# Wacky_Racers_87557913.net
KiCad netlist of a schematic drawn in Altium Designer
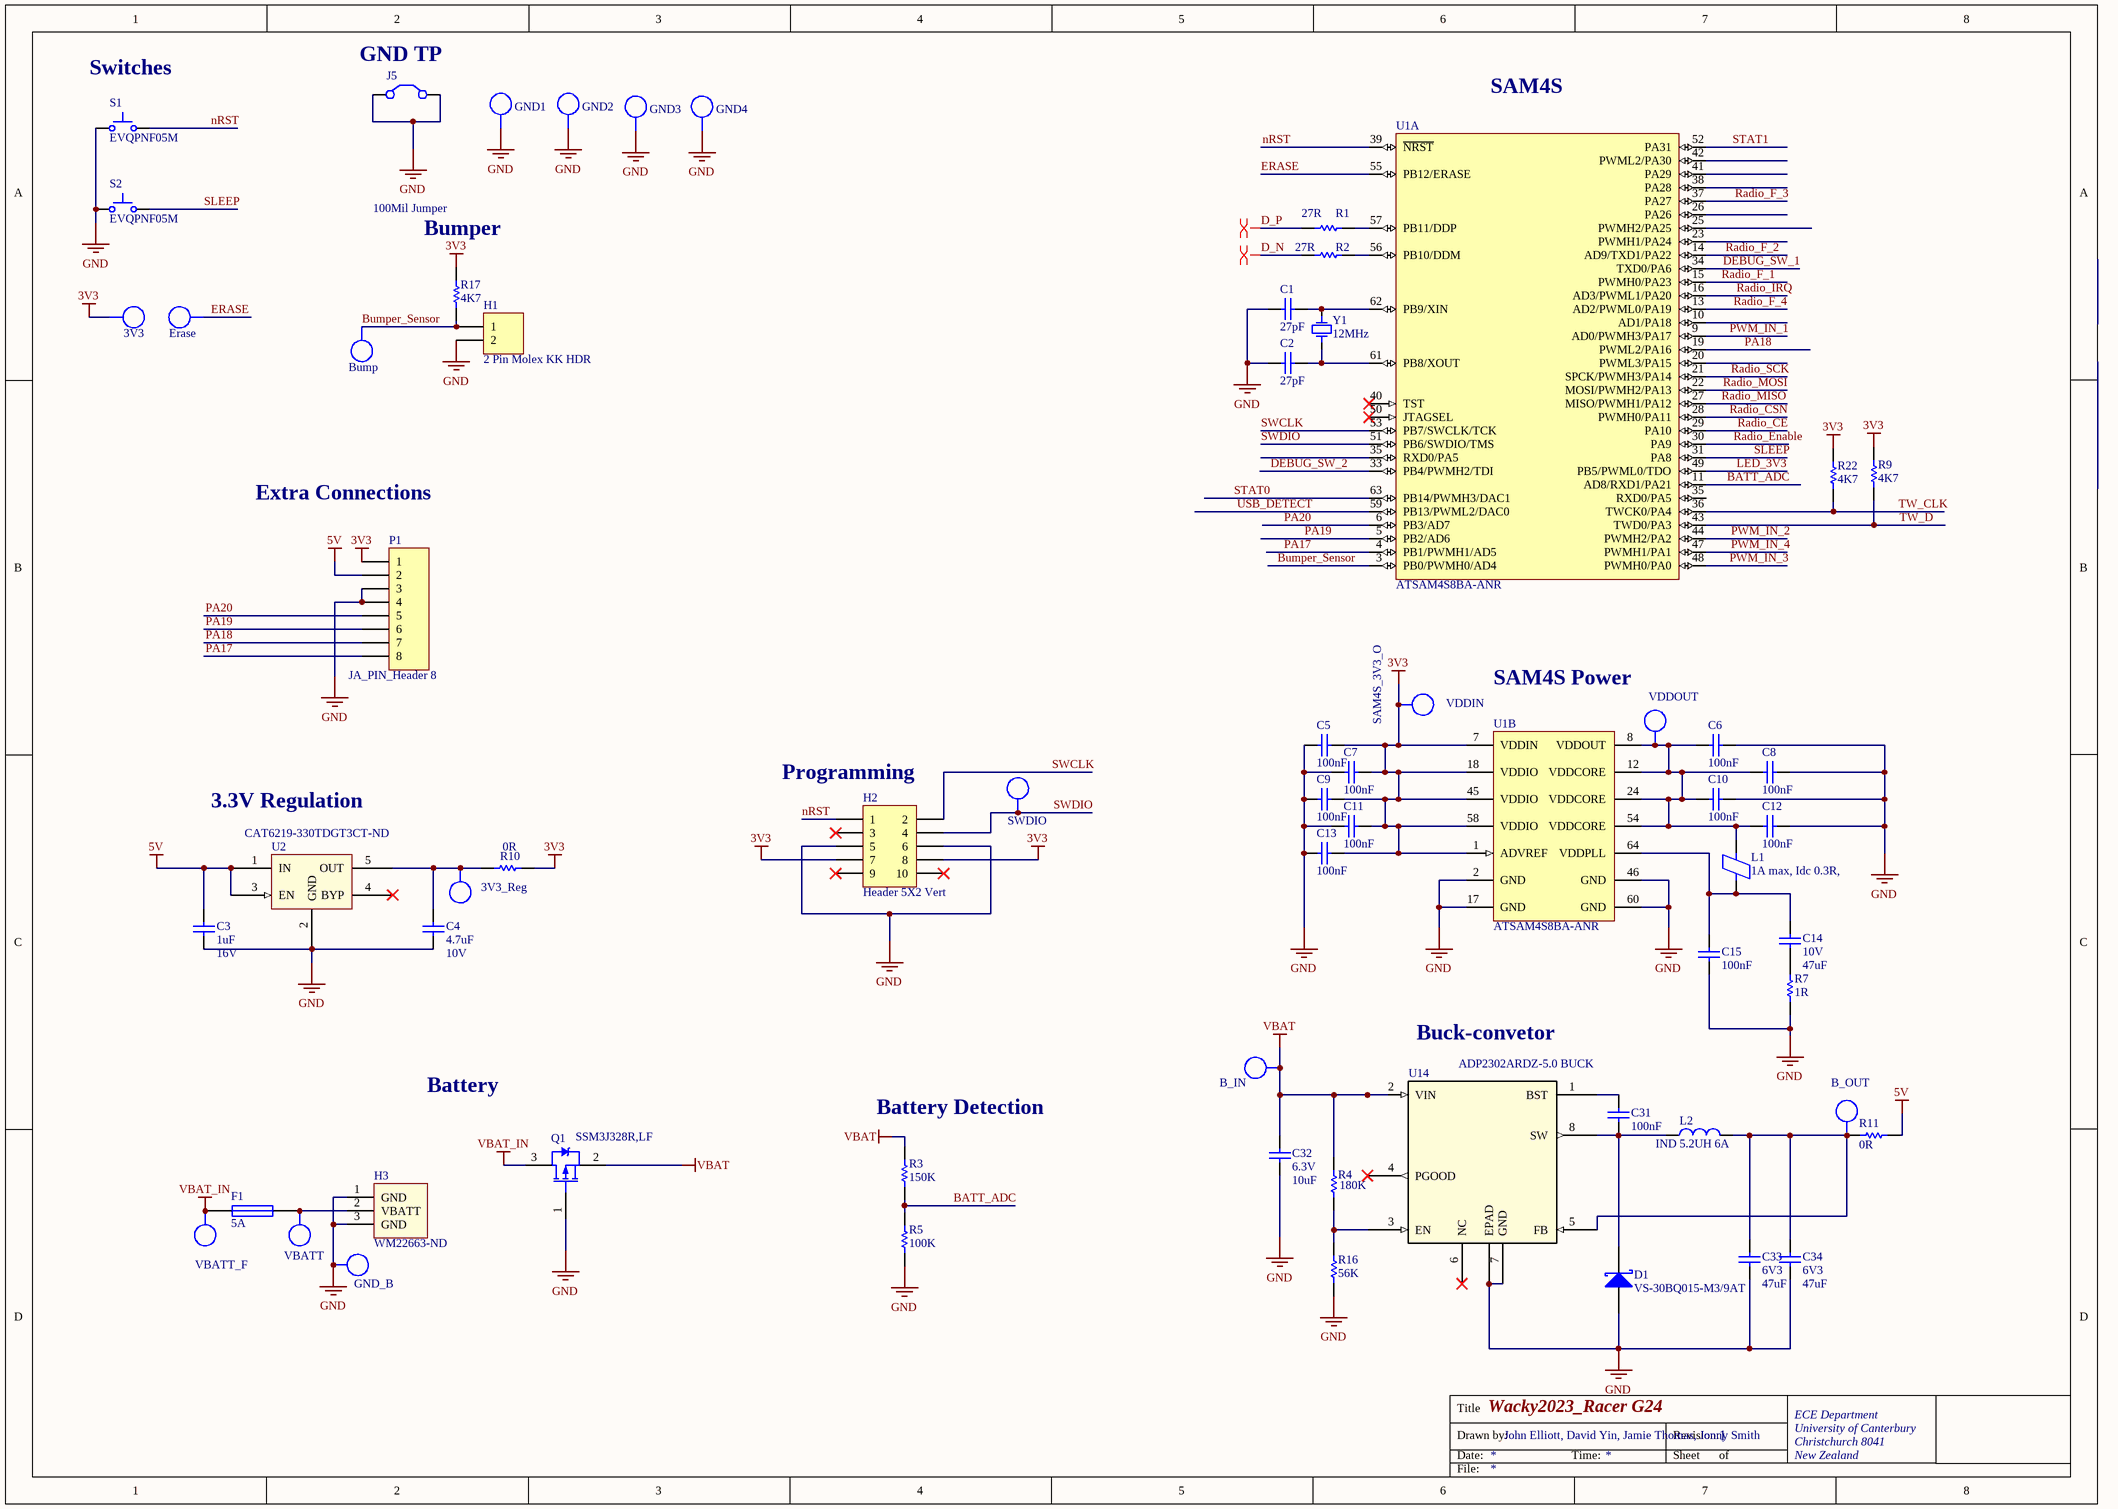
[diagram p0: Wacky_Racers_87557913.SchDoc]

(export (version "E")
  (design (tool "Eeschema 10.0.6"))
  (components
    (comp (ref "3V3")
      (value "TP")
      (footprint "TP_1206")
      (description "Test-Point 3.3x1.6x2.1mm SMD")
      (fields
        (field (name "MANUFACTURER") "Harwin Inc")
        (field (name "MANUFACTURER PART NUMBER") "S1751-46R")
      )
      (libsource (lib "ECE AD19Components_22V1") (part "TP_1206"))
    )
    (comp (ref "3V3_Reg")
      (value "TP")
      (footprint "TP_1206")
      (description "Test-Point 3.3x1.6x2.1mm SMD")
      (fields
        (field (name "MANUFACTURER") "Harwin Inc")
        (field (name "MANUFACTURER PART NUMBER") "S1751-46R")
      )
      (libsource (lib "ECE AD19Components_22V1") (part "TP_1206"))
    )
    (comp (ref "Bump")
      (value "TP")
      (footprint "TP_1206")
      (description "Test-Point 3.3x1.6x2.1mm SMD")
      (fields
        (field (name "MANUFACTURER") "Harwin Inc")
        (field (name "MANUFACTURER PART NUMBER") "S1751-46R")
      )
      (libsource (lib "ECE AD19Components_22V1") (part "TP_1206"))
    )
    (comp (ref "B_IN")
      (value "TP")
      (footprint "TP_1206")
      (description "Test-Point 3.3x1.6x2.1mm SMD")
      (fields
        (field (name "MANUFACTURER") "Harwin Inc")
        (field (name "MANUFACTURER PART NUMBER") "S1751-46R")
      )
      (libsource (lib "ECE AD19Components_22V1") (part "TP_1206"))
    )
    (comp (ref "B_OUT")
      (value "TP")
      (footprint "TP_1206")
      (description "Test-Point 3.3x1.6x2.1mm SMD")
      (fields
        (field (name "MANUFACTURER") "Harwin Inc")
        (field (name "MANUFACTURER PART NUMBER") "S1751-46R")
      )
      (libsource (lib "ECE AD19Components_22V1") (part "TP_1206"))
    )
    (comp (ref "C1")
      (value "27pF")
      (footprint "CAPC1608L")
      (description "CAP CER 27pF NPO/COG +-5% 50V 0603")
      (libsource (lib "ECE AD19Components_22V1") (part "CC_27pF_0603"))
    )
    (comp (ref "C2")
      (value "27pF")
      (footprint "CAPC1608L")
      (description "CAP CER 27pF NPO/COG +-5% 50V 0603")
      (libsource (lib "ECE AD19Components_22V1") (part "CC_27pF_0603"))
    )
    (comp (ref "C3")
      (value "1uF")
      (footprint "CAPC1608L")
      (description "CAP CER 1uF Y5V -20% +80% 16V 0603")
      (fields (field (name "MAX VOLTAGE") "16V"))
      (libsource (lib "ECE AD19Components_22V1") (part "CC_1uF_0603"))
    )
    (comp (ref "C4")
      (value "4.7uF")
      (footprint "CAPC1608N")
      (description "CAP CER 4.7uF X5R +-20%  10V 0603")
      (fields (field (name "MAX VOLTAGE") "10V"))
      (libsource (lib "ECE AD19Components_22V1") (part "CC_4.7uF_0603"))
    )
    (comp (ref "C5")
      (value "100nF")
      (footprint "CAPC1608L")
      (description "CAP CER 100nF X7R +-10% 50V 0603")
      (libsource (lib "ECE AD19Components_22V1") (part "CC_100nF_0603"))
    )
    (comp (ref "C6")
      (value "100nF")
      (footprint "CAPC1608L")
      (description "CAP CER 100nF X7R +-10% 50V 0603")
      (libsource (lib "ECE AD19Components_22V1") (part "CC_100nF_0603"))
    )
    (comp (ref "C7")
      (value "100nF")
      (footprint "CAPC1608L")
      (description "CAP CER 100nF X7R +-10% 50V 0603")
      (libsource (lib "ECE AD19Components_22V1") (part "CC_100nF_0603"))
    )
    (comp (ref "C8")
      (value "100nF")
      (footprint "CAPC1608L")
      (description "CAP CER 100nF X7R +-10% 50V 0603")
      (libsource (lib "ECE AD19Components_22V1") (part "CC_100nF_0603"))
    )
    (comp (ref "C9")
      (value "100nF")
      (footprint "CAPC1608L")
      (description "CAP CER 100nF X7R +-10% 50V 0603")
      (libsource (lib "ECE AD19Components_22V1") (part "CC_100nF_0603"))
    )
    (comp (ref "C10")
      (value "100nF")
      (footprint "CAPC1608L")
      (description "CAP CER 100nF X7R +-10% 50V 0603")
      (libsource (lib "ECE AD19Components_22V1") (part "CC_100nF_0603"))
    )
    (comp (ref "C11")
      (value "100nF")
      (footprint "CAPC1608L")
      (description "CAP CER 100nF X7R +-10% 50V 0603")
      (libsource (lib "ECE AD19Components_22V1") (part "CC_100nF_0603"))
    )
    (comp (ref "C12")
      (value "100nF")
      (footprint "CAPC1608L")
      (description "CAP CER 100nF X7R +-10% 50V 0603")
      (libsource (lib "ECE AD19Components_22V1") (part "CC_100nF_0603"))
    )
    (comp (ref "C13")
      (value "100nF")
      (footprint "CAPC1608L")
      (description "CAP CER 100nF X7R +-10% 50V 0603")
      (libsource (lib "ECE AD19Components_22V1") (part "CC_100nF_0603"))
    )
    (comp (ref "C14")
      (value "47uF")
      (footprint "CAPC3216L")
      (description "CAP CER 47uF X5R -/+20% 10V 1206")
      (fields (field (name "MAX VOLTAGE") "10V"))
      (libsource (lib "ECE AD19Components_22V1") (part "CC_47uF_1206"))
    )
    (comp (ref "C15")
      (value "100nF")
      (footprint "CAPC1608L")
      (description "CAP CER 100nF X7R +-10% 50V 0603")
      (libsource (lib "ECE AD19Components_22V1") (part "CC_100nF_0603"))
    )
    (comp (ref "C31")
      (value "100nF")
      (footprint "CAPC1608L")
      (description "CAP CER 100nF X7R +-10% 50V 0603")
      (libsource (lib "ECE AD19Components_22V1") (part "CC_100nF_0603"))
    )
    (comp (ref "C32")
      (value "10uF")
      (footprint "CAPC1608L")
      (description "CAP CER 10UF X5R +-20% 6V3 0603")
      (fields (field (name "VOLTAGE - RATED") "6.3V"))
      (libsource (lib "ECE AD19Components_22V1") (part "CC_10uF_0603"))
    )
    (comp (ref "C33")
      (value "CC_47uF_0805_6V3")
      (footprint "CAPC2012N")
      (description "SAMSUNG ELECTRO-MECHANICS - CL21A476MQCLRNC - CAP, 47UF, 6.3V, MLCC, 0805")
      (fields
        (field (name "TOLERANCE") "20%")
        (field (name "VOLTAGE RATING") "6V3")
        (field (name "CAPACITANCE") "47uF")
      )
      (libsource (lib "ECE AD19Components_22V1") (part "CC_47uF_0805_6V3"))
    )
    (comp (ref "C34")
      (value "CC_47uF_0805_6V3")
      (footprint "CAPC2012N")
      (description "SAMSUNG ELECTRO-MECHANICS - CL21A476MQCLRNC - CAP, 47UF, 6.3V, MLCC, 0805")
      (fields
        (field (name "TOLERANCE") "20%")
        (field (name "VOLTAGE RATING") "6V3")
        (field (name "CAPACITANCE") "47uF")
      )
      (libsource (lib "ECE AD19Components_22V1") (part "CC_47uF_0805_6V3"))
    )
    (comp (ref "D1")
      (value "VS-30BQ015-M3/9AT")
      (footprint "SMC")
      (description "DIODE, SCHOTTKY, 3A, 15V, DO-214AB / SMC")
      (fields (field (name "MANUFACTURER") "Vishay Semiconductors"))
      (libsource (lib "ECE AD19Components_22V1") (part "DS_VS-30BQ015-M3"))
    )
    (comp (ref "Erase")
      (value "TP")
      (footprint "TP_1206")
      (description "Test-Point 3.3x1.6x2.1mm SMD")
      (fields
        (field (name "MANUFACTURER") "Harwin Inc")
        (field (name "MANUFACTURER PART NUMBER") "S1751-46R")
      )
      (libsource (lib "ECE AD19Components_22V1") (part "TP_1206"))
    )
    (comp (ref "F1")
      (value "5A")
      (footprint "RESC3216N")
      (description "Fuse 5.0A Fast Acting 1206 SMD")
      (fields (field (name "MANUFACTURER PART NUMBER") "C1F5") (field (name "MANUFACTURER") "Bel TRP"))
      (libsource (lib "ECE AD19Components_22V1") (part "FS_Fuse_5.0A"))
    )
    (comp (ref "GND1")
      (value "TP")
      (footprint "TP_1206")
      (description "Test-Point 3.3x1.6x2.1mm SMD")
      (fields
        (field (name "MANUFACTURER") "Harwin Inc")
        (field (name "MANUFACTURER PART NUMBER") "S1751-46R")
      )
      (libsource (lib "ECE AD19Components_22V1") (part "TP_1206"))
    )
    (comp (ref "GND2")
      (value "TP")
      (footprint "TP_1206")
      (description "Test-Point 3.3x1.6x2.1mm SMD")
      (fields
        (field (name "MANUFACTURER") "Harwin Inc")
        (field (name "MANUFACTURER PART NUMBER") "S1751-46R")
      )
      (libsource (lib "ECE AD19Components_22V1") (part "TP_1206"))
    )
    (comp (ref "GND3")
      (value "TP")
      (footprint "TP_1206")
      (description "Test-Point 3.3x1.6x2.1mm SMD")
      (fields
        (field (name "MANUFACTURER") "Harwin Inc")
        (field (name "MANUFACTURER PART NUMBER") "S1751-46R")
      )
      (libsource (lib "ECE AD19Components_22V1") (part "TP_1206"))
    )
    (comp (ref "GND4")
      (value "TP")
      (footprint "TP_1206")
      (description "Test-Point 3.3x1.6x2.1mm SMD")
      (fields
        (field (name "MANUFACTURER") "Harwin Inc")
        (field (name "MANUFACTURER PART NUMBER") "S1751-46R")
      )
      (libsource (lib "ECE AD19Components_22V1") (part "TP_1206"))
    )
    (comp (ref "GND_B")
      (value "TP")
      (footprint "TP_1206")
      (description "Test-Point 3.3x1.6x2.1mm SMD")
      (fields
        (field (name "MANUFACTURER") "Harwin Inc")
        (field (name "MANUFACTURER PART NUMBER") "S1751-46R")
      )
      (libsource (lib "ECE AD19Components_22V1") (part "TP_1206"))
    )
    (comp (ref "H1")
      (value "2 Pin Molex KK HDR")
      (footprint "MOLEX_KK_2_HDR")
      (description "CONN HEADER 2POS 2.54mm VERT_Thru Hole")
      (libsource (lib "ECE AD19Components_22V1") (part "JA_MOLEX_KK_2POS"))
    )
    (comp (ref "H2")
      (value "Header 5X2 Vert")
      (footprint "IDC2.54-V10D")
      (description "IDC Header, 2,54mm, 10-Pin, Vert")
      (libsource (lib "ECE AD19Components_22V1") (part "JA_HDR_IDC_5X2_VERT"))
    )
    (comp (ref "H3")
      (value "Battery_HEADER_3pin")
      (footprint "BATT_HEADER_3POS")
      (description "3Pin Header 2.54mm spacing\r\nDigikey #WM22663-ND")
      (fields (field (name "SUPPLIER PART NUMBER 1") "WM22663-ND"))
      (libsource (lib "ENCE461AD19_V23") (part "Battery_HEADER_3pin"))
    )
    (comp (ref "J5")
      (value "100Mil Jumper")
      (footprint "JMP2.54")
      (description "2.54mm Jumper Thru Hole")
      (libsource (lib "ECE AD19Components_22V1") (part "TP_JUMPER"))
    )
    (comp (ref "L1")
      (value "1A max, Idc 0.3R,")
      (footprint "INDC3216L")
      (description "Ferrite Bead, Rdc 0.3R, Z100MHZ 600R, Imax 1A, SMD 1206")
      (fields
        (field (name "MANUFACTURER") "FAIR-RITE")
        (field (name "MANUFACTURER PART NUMBER") "2512066017Y1")
      )
      (libsource (lib "ECE AD19Components_22V1") (part "IN_Ferrite-Bead"))
    )
    (comp (ref "L2")
      (value "IND 5.2UH 6A")
      (footprint "INDUCTOR5u2")
      (description "FIXED IND 5.2UH 6A 22 MOHM SMD")
      (fields
        (field (name "MANUFACTURER") "Sumida America Components Inc.")
        (field (name "MANUFACTURER PART NUMBER") "CDRH104RNP-5R2NC")
      )
      (libsource (lib "ENCE461AD19_V23") (part "CDRH104RNP-5R2NC"))
    )
    (comp (ref "P1")
      (value "JA_PIN_Header 8")
      (footprint "HDR1X8")
      (description "Header, 8-Pin")
      (fields (field (name "PUBLISHER") "Altium Limited"))
      (libsource (lib "ECE AD19Components_22V1") (part "JA_PIN_Header 8"))
    )
    (comp (ref "Q1")
      (value "SSM3J328R,LF")
      (footprint "SOT23_L")
      (description "MOSFET P-CH 20V 6A SOT23-3")
      (fields
        (field (name "MANUFACTURER") "Toshiba")
        (field (name "MANUFACTURER PART NUMBER") "SSM3J328R,LF")
      )
      (libsource (lib "ECE AD19Components_22V1") (part "TM_SSM3J328R"))
    )
    (comp (ref "R1")
      (value "27R")
      (footprint "RESC1608L")
      (description "RES 27 OHM 1/10W 5% 0603 SMD")
      (libsource (lib "ECE AD19Components_22V1") (part "RS_27R"))
    )
    (comp (ref "R2")
      (value "27R")
      (footprint "RESC1608L")
      (description "RES 27 OHM 1/10W 5% 0603 SMD")
      (libsource (lib "ECE AD19Components_22V1") (part "RS_27R"))
    )
    (comp (ref "R3")
      (value "150K")
      (footprint "RESC1608L")
      (description "RES 150K OHM 1/10W 5% 0603 SMD")
      (libsource (lib "ECE AD19Components_22V1") (part "RS_150K"))
    )
    (comp (ref "R4")
      (value "180K")
      (footprint "RESC1608L")
      (description "RES 180K OHM 1/10W 5% 0603 SMD")
      (libsource (lib "ECE AD19Components_22V1") (part "RS_180K"))
    )
    (comp (ref "R5")
      (value "100K")
      (footprint "RESC1608L")
      (description "RES 100K OHM 1/10W 5% 0603 SMD")
      (libsource (lib "ECE AD19Components_22V1") (part "RS_100K"))
    )
    (comp (ref "R7")
      (value "1R")
      (footprint "RESC3216L")
      (description "RES 1R OHM 1/4W 5% 1206 SMD")
      (libsource (lib "ECE AD19Components_22V1") (part "RT_1R"))
    )
    (comp (ref "R9")
      (value "4K7")
      (footprint "RESC1608L")
      (description "RES 4.7K OHM 1/10W 5% 0603 SMD")
      (libsource (lib "ECE AD19Components_22V1") (part "RS_4K7"))
    )
    (comp (ref "R10")
      (value "0R")
      (footprint "RESC1608L")
      (description "RES 0.0 OHM 1/10W 5% 0603 SMD")
      (libsource (lib "ECE AD19Components_22V1") (part "RS_0R0"))
    )
    (comp (ref "R11")
      (value "0R")
      (footprint "RESC1608L")
      (description "RES 0.0 OHM 1/10W 5% 0603 SMD")
      (libsource (lib "ECE AD19Components_22V1") (part "RS_0R0"))
    )
    (comp (ref "R16")
      (value "56K")
      (footprint "RESC1608L")
      (description "RES 56.0K OHM 1/10W 5% 0603 SMD")
      (libsource (lib "ECE AD19Components_22V1") (part "RS_56K"))
    )
    (comp (ref "R17")
      (value "4K7")
      (footprint "RESC1608L")
      (description "RES 4.7K OHM 1/10W 5% 0603 SMD")
      (libsource (lib "ECE AD19Components_22V1") (part "RS_4K7"))
    )
    (comp (ref "R22")
      (value "4K7")
      (footprint "RESC1608L")
      (description "RES 4.7K OHM 1/10W 5% 0603 SMD")
      (libsource (lib "ECE AD19Components_22V1") (part "RS_4K7"))
    )
    (comp (ref "S1")
      (value "EVQPNF05M")
      (footprint "EVQPNF05M")
      (description "Panasonic 6 x 3.5mm SMD Light Touch Switch Type SMD")
      (fields (field (name "MANUFACTURER") "Panasonic"))
      (libsource (lib "ECE AD19Components_22V1") (part "WS_EVQPNF05M"))
    )
    (comp (ref "S2")
      (value "EVQPNF05M")
      (footprint "EVQPNF05M")
      (description "Panasonic 6 x 3.5mm SMD Light Touch Switch Type SMD")
      (fields (field (name "MANUFACTURER") "Panasonic"))
      (libsource (lib "ECE AD19Components_22V1") (part "WS_EVQPNF05M"))
    )
    (comp (ref "SWDIO")
      (value "TP")
      (footprint "TP_1206")
      (description "Test-Point 3.3x1.6x2.1mm SMD")
      (fields
        (field (name "MANUFACTURER") "Harwin Inc")
        (field (name "MANUFACTURER PART NUMBER") "S1751-46R")
      )
      (libsource (lib "ECE AD19Components_22V1") (part "TP_1206"))
    )
    (comp (ref "U1")
      (value "ATSAM4S8BA-ANR")
      (footprint "LQFP64_L")
      (description "IC MCU 32BIT 512KB FLASH 64LQFP")
      (fields (field (name "MANUFACTURER") "Atmel"))
      (libsource (lib "ECE AD19Components_22V1") (part "SE_ATSAM4S16BA-MU"))
    )
    (comp (ref "U2")
      (value "CAT6219-330TDGT3")
      (footprint "SOT95P280X145-5N")
      (description "IC REG LIN 3.3V 500MA TSOT23-5")
      (fields
        (field (name "BASE PART NUMBER") "CAT6219")
        (field (name "SUPPLIER PART NUMBER") "CAT6219-330TDGT3CT-ND")
      )
      (libsource (lib "ENCE461AD19_V23") (part "SV_CAT6219-330TDGT3"))
    )
    (comp (ref "U14")
      (value "ADP2302ARDZ-5.0 BUCK")
      (footprint "RD_8_1")
      (description "IC REG BUCK 5V 2A 8SOIC")
      (fields (field (name "MANUFACTURER_PART_NUMBER") "ADP2302ARDZ-5.0-R7"))
      (libsource (lib "ENCE461AD19_V23") (part "ADP2302ARDZ-5.0-R7"))
    )
    (comp (ref "VBATT")
      (value "TP")
      (footprint "TP_1206")
      (description "Test-Point 3.3x1.6x2.1mm SMD")
      (fields
        (field (name "MANUFACTURER") "Harwin Inc")
        (field (name "MANUFACTURER PART NUMBER") "S1751-46R")
      )
      (libsource (lib "ECE AD19Components_22V1") (part "TP_1206"))
    )
    (comp (ref "VBATT_F")
      (value "TP")
      (footprint "TP_1206")
      (description "Test-Point 3.3x1.6x2.1mm SMD")
      (fields
        (field (name "MANUFACTURER") "Harwin Inc")
        (field (name "MANUFACTURER PART NUMBER") "S1751-46R")
      )
      (libsource (lib "ECE AD19Components_22V1") (part "TP_1206"))
    )
    (comp (ref "VDDIN")
      (value "TP")
      (footprint "TP_1206")
      (description "Test-Point 3.3x1.6x2.1mm SMD")
      (fields
        (field (name "MANUFACTURER") "Harwin Inc")
        (field (name "MANUFACTURER PART NUMBER") "S1751-46R")
      )
      (libsource (lib "ECE AD19Components_22V1") (part "TP_1206"))
    )
    (comp (ref "VDDOUT")
      (value "TP")
      (footprint "TP_1206")
      (description "Test-Point 3.3x1.6x2.1mm SMD")
      (fields
        (field (name "MANUFACTURER") "Harwin Inc")
        (field (name "MANUFACTURER PART NUMBER") "S1751-46R")
      )
      (libsource (lib "ECE AD19Components_22V1") (part "TP_1206"))
    )
    (comp (ref "Y1")
      (value "12MHz")
      (footprint "6.0X3.5-4")
      (description "CRYSTAL 12MHZ 18PF 6X3.5mm SMD")
      (fields
        (field (name "MANUFACTURER") "CTS-Frequency Controls")
        (field (name "MANUFACTURER PART NUMBER") "406C35D12M00000")
        (field (name "FREQUENCY") "12MHz")
      )
      (libsource (lib "ECE AD19Components_22V1") (part "XT_CRYSTAL_12MHz_18pF"))
    )
  )
  (nets
    (net (code "1") (name "/BATT_ADC") (class "Default")
      (node (ref "R3") (pin "1") (pinfunction "1_1") (pintype "passive"))
      (node (ref "R5") (pin "2") (pinfunction "2_2") (pintype "passive"))
      (node (ref "U1") (pin "11") (pinfunction "AD8/RXD1/PA21_11") (pintype "bidirectional"))
    )
    (net (code "2") (name "/Bumper_Sensor") (class "Default")
      (node (ref "Bump") (pin "1") (pinfunction "1_1") (pintype "passive"))
      (node (ref "H1") (pin "1") (pinfunction "1_1") (pintype "passive"))
      (node (ref "R17") (pin "1") (pinfunction "1_1") (pintype "passive"))
      (node (ref "U1") (pin "3") (pinfunction "PB0/PWMH0/AD4_3") (pintype "bidirectional"))
    )
    (net (code "3") (name "/DEBUG_SW_1") (class "Default")
      (node (ref "U1") (pin "34") (pinfunction "TXD0/PA6_34") (pintype "bidirectional"))
    )
    (net (code "4") (name "/DEBUG_SW_2") (class "Default")
      (node (ref "U1") (pin "33") (pinfunction "PB4/PWMH2/TDI_33") (pintype "bidirectional"))
    )
    (net (code "5") (name "/D_N") (class "Default")
      (node (ref "R2") (pin "1") (pinfunction "1_1") (pintype "passive"))
    )
    (net (code "6") (name "/D_P") (class "Default")
      (node (ref "R1") (pin "1") (pinfunction "1_1") (pintype "passive"))
    )
    (net (code "7") (name "/ERASE") (class "Default")
      (node (ref "Erase") (pin "1") (pinfunction "1_1") (pintype "passive"))
      (node (ref "U1") (pin "55") (pinfunction "PB12/ERASE_55") (pintype "bidirectional"))
    )
    (net (code "8") (name "/LED_3V3") (class "Default")
      (node (ref "U1") (pin "49") (pinfunction "PB5/PWML0/TDO_49") (pintype "bidirectional"))
    )
    (net (code "9") (name "/PA17") (class "Default")
      (node (ref "P1") (pin "8") (pinfunction "8_8") (pintype "passive"))
      (node (ref "U1") (pin "4") (pinfunction "PB1/PWMH1/AD5_4") (pintype "bidirectional"))
    )
    (net (code "10") (name "/PA18") (class "Default")
      (node (ref "P1") (pin "7") (pinfunction "7_7") (pintype "passive"))
      (node (ref "U1") (pin "19") (pinfunction "PWML2/PA16_19") (pintype "bidirectional"))
    )
    (net (code "11") (name "/PA19") (class "Default")
      (node (ref "P1") (pin "6") (pinfunction "6_6") (pintype "passive"))
      (node (ref "U1") (pin "5") (pinfunction "PB2/AD6_5") (pintype "bidirectional"))
    )
    (net (code "12") (name "/PA20") (class "Default")
      (node (ref "P1") (pin "5") (pinfunction "5_5") (pintype "passive"))
      (node (ref "U1") (pin "6") (pinfunction "PB3/AD7_6") (pintype "bidirectional"))
    )
    (net (code "13") (name "/PWM_IN_1") (class "Default")
      (node (ref "U1") (pin "9") (pinfunction "AD0/PWMH3/PA17_9") (pintype "bidirectional"))
    )
    (net (code "14") (name "/PWM_IN_2") (class "Default")
      (node (ref "U1") (pin "44") (pinfunction "PWMH2/PA2_44") (pintype "bidirectional"))
    )
    (net (code "15") (name "/PWM_IN_3") (class "Default")
      (node (ref "U1") (pin "48") (pinfunction "PWMH0/PA0_48") (pintype "bidirectional"))
    )
    (net (code "16") (name "/PWM_IN_4") (class "Default")
      (node (ref "U1") (pin "47") (pinfunction "PWMH1/PA1_47") (pintype "bidirectional"))
    )
    (net (code "17") (name "/Radio_CE") (class "Default")
      (node (ref "U1") (pin "29") (pinfunction "PA10_29") (pintype "bidirectional"))
    )
    (net (code "18") (name "/Radio_CSN") (class "Default")
      (node (ref "U1") (pin "28") (pinfunction "PWMH0/PA11_28") (pintype "bidirectional"))
    )
    (net (code "19") (name "/Radio_Enable") (class "Default")
      (node (ref "U1") (pin "30") (pinfunction "PA9_30") (pintype "bidirectional"))
    )
    (net (code "20") (name "/Radio_F_1") (class "Default")
      (node (ref "U1") (pin "15") (pinfunction "PWMH0/PA23_15") (pintype "bidirectional"))
    )
    (net (code "21") (name "/Radio_F_2") (class "Default")
      (node (ref "U1") (pin "14") (pinfunction "AD9/TXD1/PA22_14") (pintype "bidirectional"))
    )
    (net (code "22") (name "/Radio_F_3") (class "Default")
      (node (ref "U1") (pin "37") (pinfunction "PA27_37") (pintype "bidirectional"))
    )
    (net (code "23") (name "/Radio_F_4") (class "Default")
      (node (ref "U1") (pin "13") (pinfunction "AD2/PWML0/PA19_13") (pintype "bidirectional"))
    )
    (net (code "24") (name "/Radio_IRQ") (class "Default")
      (node (ref "U1") (pin "16") (pinfunction "AD3/PWML1/PA20_16") (pintype "bidirectional"))
    )
    (net (code "25") (name "/Radio_MISO") (class "Default")
      (node (ref "U1") (pin "27") (pinfunction "MISO/PWMH1/PA12_27") (pintype "bidirectional"))
    )
    (net (code "26") (name "/Radio_MOSI") (class "Default")
      (node (ref "U1") (pin "22") (pinfunction "MOSI/PWMH2/PA13_22") (pintype "bidirectional"))
    )
    (net (code "27") (name "/Radio_SCK") (class "Default")
      (node (ref "U1") (pin "21") (pinfunction "SPCK/PWMH3/PA14_21") (pintype "bidirectional"))
    )
    (net (code "28") (name "/SLEEP") (class "Default")
      (node (ref "S2") (pin "2") (pintype "passive"))
      (node (ref "U1") (pin "31") (pinfunction "PA8_31") (pintype "bidirectional"))
    )
    (net (code "29") (name "/STAT0") (class "Default")
      (node (ref "U1") (pin "63") (pinfunction "PB14/PWMH3/DAC1_63") (pintype "bidirectional"))
    )
    (net (code "30") (name "/STAT1") (class "Default")
      (node (ref "U1") (pin "52") (pinfunction "PA31_52") (pintype "bidirectional"))
    )
    (net (code "31") (name "/SWCLK") (class "Default")
      (node (ref "H2") (pin "2") (pinfunction "2_2") (pintype "passive"))
      (node (ref "U1") (pin "53") (pinfunction "PB7/SWCLK/TCK_53") (pintype "bidirectional"))
    )
    (net (code "32") (name "/SWDIO") (class "Default")
      (node (ref "H2") (pin "4") (pinfunction "4_4") (pintype "passive"))
      (node (ref "SWDIO") (pin "1") (pinfunction "1_1") (pintype "passive"))
      (node (ref "U1") (pin "51") (pinfunction "PB6/SWDIO/TMS_51") (pintype "bidirectional"))
    )
    (net (code "33") (name "/TW_CLK") (class "Default")
      (node (ref "R22") (pin "2") (pinfunction "2_2") (pintype "passive"))
      (node (ref "U1") (pin "36") (pinfunction "TWCK0/PA4_36") (pintype "bidirectional"))
    )
    (net (code "34") (name "/TW_D") (class "Default")
      (node (ref "R9") (pin "2") (pinfunction "2_2") (pintype "passive"))
      (node (ref "U1") (pin "43") (pinfunction "TWD0/PA3_43") (pintype "bidirectional"))
    )
    (net (code "35") (name "/USB_DETECT") (class "Default")
      (node (ref "U1") (pin "59") (pinfunction "PB13/PWML2/DAC0_59") (pintype "bidirectional"))
    )
    (net (code "36") (name "/nRST") (class "Default")
      (node (ref "H2") (pin "1") (pinfunction "1_1") (pintype "passive"))
      (node (ref "S1") (pin "2") (pintype "passive"))
      (node (ref "U1") (pin "39") (pinfunction "~{NRST}_39") (pintype "bidirectional"))
    )
    (net (code "37") (name "3V3") (class "Default")
      (node (ref "3V3") (pin "1") (pinfunction "1_1") (pintype "passive"))
      (node (ref "C11") (pin "2") (pinfunction "2_2") (pintype "passive"))
      (node (ref "C13") (pin "1") (pinfunction "1_1") (pintype "passive"))
      (node (ref "C5") (pin "2") (pinfunction "2_2") (pintype "passive"))
      (node (ref "C7") (pin "2") (pinfunction "2_2") (pintype "passive"))
      (node (ref "C9") (pin "2") (pinfunction "2_2") (pintype "passive"))
      (node (ref "H2") (pin "7") (pinfunction "7_7") (pintype "passive"))
      (node (ref "H2") (pin "8") (pinfunction "8_8") (pintype "passive"))
      (node (ref "P1") (pin "1") (pinfunction "1_1") (pintype "passive"))
      (node (ref "R10") (pin "2") (pinfunction "2_2") (pintype "passive"))
      (node (ref "R17") (pin "2") (pinfunction "2_2") (pintype "passive"))
      (node (ref "R22") (pin "1") (pinfunction "1_1") (pintype "passive"))
      (node (ref "R9") (pin "1") (pinfunction "1_1") (pintype "passive"))
      (node (ref "U1") (pin "1") (pinfunction "ADVREF_1") (pintype "input"))
      (node (ref "U1") (pin "18") (pinfunction "VDDIO_18") (pintype "power_in"))
      (node (ref "U1") (pin "45") (pinfunction "VDDIO_45") (pintype "power_in"))
      (node (ref "U1") (pin "58") (pinfunction "VDDIO_58") (pintype "power_in"))
      (node (ref "U1") (pin "7") (pinfunction "VDDIN_7") (pintype "power_in"))
      (node (ref "VDDIN") (pin "1") (pinfunction "1_1") (pintype "passive"))
    )
    (net (code "38") (name "5V") (class "Default")
      (node (ref "C3") (pin "2") (pinfunction "2_2") (pintype "passive"))
      (node (ref "P1") (pin "2") (pinfunction "2_2") (pintype "passive"))
      (node (ref "R11") (pin "1") (pinfunction "1_1") (pintype "passive"))
      (node (ref "U2") (pin "1") (pinfunction "IN_1") (pintype "power_in"))
      (node (ref "U2") (pin "3") (pinfunction "EN_3") (pintype "input"))
    )
    (net (code "39") (name "GND") (class "Default")
      (node (ref "C1") (pin "1") (pinfunction "1_1") (pintype "passive"))
      (node (ref "C10") (pin "2") (pinfunction "2_2") (pintype "passive"))
      (node (ref "C11") (pin "1") (pinfunction "1_1") (pintype "passive"))
      (node (ref "C12") (pin "2") (pinfunction "2_2") (pintype "passive"))
      (node (ref "C13") (pin "2") (pinfunction "2_2") (pintype "passive"))
      (node (ref "C15") (pin "1") (pinfunction "1_1") (pintype "passive"))
      (node (ref "C2") (pin "1") (pinfunction "1_1") (pintype "passive"))
      (node (ref "C3") (pin "1") (pinfunction "1_1") (pintype "passive"))
      (node (ref "C32") (pin "1") (pinfunction "1_1") (pintype "passive"))
      (node (ref "C33") (pin "1") (pinfunction "1_1") (pintype "passive"))
      (node (ref "C34") (pin "1") (pinfunction "1_1") (pintype "passive"))
      (node (ref "C4") (pin "1") (pinfunction "1_1") (pintype "passive"))
      (node (ref "C5") (pin "1") (pinfunction "1_1") (pintype "passive"))
      (node (ref "C6") (pin "2") (pinfunction "2_2") (pintype "passive"))
      (node (ref "C7") (pin "1") (pinfunction "1_1") (pintype "passive"))
      (node (ref "C8") (pin "2") (pinfunction "2_2") (pintype "passive"))
      (node (ref "C9") (pin "1") (pinfunction "1_1") (pintype "passive"))
      (node (ref "D1") (pin "1") (pinfunction "A_1") (pintype "passive"))
      (node (ref "GND1") (pin "1") (pinfunction "1_1") (pintype "passive"))
      (node (ref "GND2") (pin "1") (pinfunction "1_1") (pintype "passive"))
      (node (ref "GND3") (pin "1") (pinfunction "1_1") (pintype "passive"))
      (node (ref "GND4") (pin "1") (pinfunction "1_1") (pintype "passive"))
      (node (ref "GND_B") (pin "1") (pinfunction "1_1") (pintype "passive"))
      (node (ref "H1") (pin "2") (pinfunction "2_2") (pintype "passive"))
      (node (ref "H2") (pin "5") (pinfunction "5_5") (pintype "passive"))
      (node (ref "H2") (pin "6") (pinfunction "6_6") (pintype "passive"))
      (node (ref "H3") (pin "1") (pinfunction "GND_1") (pintype "passive"))
      (node (ref "H3") (pin "3") (pinfunction "GND_3") (pintype "passive"))
      (node (ref "J5") (pin "1") (pinfunction "C1_1") (pintype "passive"))
      (node (ref "J5") (pin "2") (pinfunction "C2_2") (pintype "passive"))
      (node (ref "P1") (pin "3") (pinfunction "3_3") (pintype "passive"))
      (node (ref "P1") (pin "4") (pinfunction "4_4") (pintype "passive"))
      (node (ref "Q1") (pin "1") (pinfunction "1_1") (pintype "passive"))
      (node (ref "R16") (pin "1") (pinfunction "1_1") (pintype "passive"))
      (node (ref "R5") (pin "1") (pinfunction "1_1") (pintype "passive"))
      (node (ref "R7") (pin "1") (pinfunction "1_1") (pintype "passive"))
      (node (ref "S1") (pin "1") (pintype "passive"))
      (node (ref "S2") (pin "1") (pintype "passive"))
      (node (ref "U1") (pin "17") (pinfunction "GND_17") (pintype "power_in"))
      (node (ref "U1") (pin "2") (pinfunction "GND_2") (pintype "power_in"))
      (node (ref "U1") (pin "46") (pinfunction "GND_46") (pintype "power_in"))
      (node (ref "U1") (pin "60") (pinfunction "GND_60") (pintype "power_in"))
      (node (ref "U14") (pin "7") (pinfunction "GND_7") (pintype "power_in"))
      (node (ref "U14") (pin "EPAD") (pinfunction "EPAD_EPAD") (pintype "passive"))
      (node (ref "U2") (pin "2") (pinfunction "GND_2") (pintype "power_in"))
    )
    (net (code "40") (name "Net-(C14-Pad1)") (class "Default")
      (node (ref "C14") (pin "1") (pinfunction "1_1") (pintype "passive"))
      (node (ref "R7") (pin "2") (pinfunction "2_2") (pintype "passive"))
    )
    (net (code "41") (name "Net-(D1-K)") (class "Default")
      (node (ref "C31") (pin "1") (pinfunction "1_1") (pintype "passive"))
      (node (ref "D1") (pin "2") (pinfunction "K_2") (pintype "passive"))
      (node (ref "L2") (pin "1") (pintype "passive"))
      (node (ref "U14") (pin "8") (pinfunction "SW_8") (pintype "output"))
    )
    (net (code "42") (name "Net-(H3-VBATT)") (class "Default")
      (node (ref "F1") (pin "2") (pinfunction "2_2") (pintype "passive"))
      (node (ref "H3") (pin "2") (pinfunction "VBATT_2") (pintype "passive"))
      (node (ref "VBATT") (pin "1") (pinfunction "1_1") (pintype "passive"))
    )
    (net (code "43") (name "Net-(U1A-PB8{slash}XOUT)") (class "Default")
      (node (ref "C2") (pin "2") (pinfunction "2_2") (pintype "passive"))
      (node (ref "U1") (pin "61") (pinfunction "PB8/XOUT_61") (pintype "bidirectional"))
      (node (ref "Y1") (pin "1") (pinfunction "OSC1_1") (pintype "passive"))
    )
    (net (code "44") (name "Net-(U1A-PB9{slash}XIN)") (class "Default")
      (node (ref "C1") (pin "2") (pinfunction "2_2") (pintype "passive"))
      (node (ref "U1") (pin "62") (pinfunction "PB9/XIN_62") (pintype "bidirectional"))
      (node (ref "Y1") (pin "3") (pinfunction "OSC2_3") (pintype "passive"))
    )
    (net (code "45") (name "Net-(U1A-PB10{slash}DDM)") (class "Default")
      (node (ref "R2") (pin "2") (pinfunction "2_2") (pintype "passive"))
      (node (ref "U1") (pin "56") (pinfunction "PB10/DDM_56") (pintype "bidirectional"))
    )
    (net (code "46") (name "Net-(U1A-PB11{slash}DDP)") (class "Default")
      (node (ref "R1") (pin "2") (pinfunction "2_2") (pintype "passive"))
      (node (ref "U1") (pin "57") (pinfunction "PB11/DDP_57") (pintype "bidirectional"))
    )
    (net (code "47") (name "Net-(U1B-VDDOUT)") (class "Default")
      (node (ref "C10") (pin "1") (pinfunction "1_1") (pintype "passive"))
      (node (ref "C12") (pin "1") (pinfunction "1_1") (pintype "passive"))
      (node (ref "C6") (pin "1") (pinfunction "1_1") (pintype "passive"))
      (node (ref "C8") (pin "1") (pinfunction "1_1") (pintype "passive"))
      (node (ref "L1") (pin "2") (pinfunction "2_2") (pintype "passive"))
      (node (ref "U1") (pin "12") (pinfunction "VDDCORE_12") (pintype "power_in"))
      (node (ref "U1") (pin "24") (pinfunction "VDDCORE_24") (pintype "power_in"))
      (node (ref "U1") (pin "54") (pinfunction "VDDCORE_54") (pintype "power_in"))
      (node (ref "U1") (pin "8") (pinfunction "VDDOUT_8") (pintype "power_in"))
      (node (ref "VDDOUT") (pin "1") (pinfunction "1_1") (pintype "passive"))
    )
    (net (code "48") (name "Net-(U1B-VDDPLL)") (class "Default")
      (node (ref "C14") (pin "2") (pinfunction "2_2") (pintype "passive"))
      (node (ref "C15") (pin "2") (pinfunction "2_2") (pintype "passive"))
      (node (ref "L1") (pin "1") (pinfunction "1_1") (pintype "passive"))
      (node (ref "U1") (pin "64") (pinfunction "VDDPLL_64") (pintype "power_in"))
    )
    (net (code "49") (name "Net-(U2-OUT)") (class "Default")
      (node (ref "3V3_Reg") (pin "1") (pinfunction "1_1") (pintype "passive"))
      (node (ref "C4") (pin "2") (pinfunction "2_2") (pintype "passive"))
      (node (ref "R10") (pin "1") (pinfunction "1_1") (pintype "passive"))
      (node (ref "U2") (pin "5") (pinfunction "OUT_5") (pintype "power_in"))
    )
    (net (code "50") (name "Net-(U14-BST)") (class "Default")
      (node (ref "C31") (pin "2") (pinfunction "2_2") (pintype "passive"))
      (node (ref "U14") (pin "1") (pinfunction "BST_1") (pintype "passive"))
    )
    (net (code "51") (name "Net-(U14-EN)") (class "Default")
      (node (ref "R16") (pin "2") (pinfunction "2_2") (pintype "passive"))
      (node (ref "R4") (pin "1") (pinfunction "1_1") (pintype "passive"))
      (node (ref "U14") (pin "3") (pinfunction "EN_3") (pintype "input"))
    )
    (net (code "52") (name "Net-(U14-FB)") (class "Default")
      (node (ref "B_OUT") (pin "1") (pinfunction "1_1") (pintype "passive"))
      (node (ref "C33") (pin "2") (pinfunction "2_2") (pintype "passive"))
      (node (ref "C34") (pin "2") (pinfunction "2_2") (pintype "passive"))
      (node (ref "L2") (pin "2") (pintype "passive"))
      (node (ref "R11") (pin "2") (pinfunction "2_2") (pintype "passive"))
      (node (ref "U14") (pin "5") (pinfunction "FB_5") (pintype "input"))
    )
    (net (code "53") (name "VBAT") (class "Default")
      (node (ref "B_IN") (pin "1") (pinfunction "1_1") (pintype "passive"))
      (node (ref "C32") (pin "2") (pinfunction "2_2") (pintype "passive"))
      (node (ref "Q1") (pin "2") (pinfunction "2_2") (pintype "passive"))
      (node (ref "R3") (pin "2") (pinfunction "2_2") (pintype "passive"))
      (node (ref "R4") (pin "2") (pinfunction "2_2") (pintype "passive"))
      (node (ref "U14") (pin "2") (pinfunction "VIN_2") (pintype "input"))
    )
    (net (code "54") (name "VBAT_IN") (class "Default")
      (node (ref "F1") (pin "1") (pinfunction "1_1") (pintype "passive"))
      (node (ref "Q1") (pin "3") (pinfunction "3_3") (pintype "passive"))
      (node (ref "VBATT_F") (pin "1") (pinfunction "1_1") (pintype "passive"))
    )
    (net (code "55") (name "unconnected-(H2-Pad3)") (class "Default")
      (node (ref "H2") (pin "3") (pinfunction "3_3") (pintype "passive+no_connect"))
    )
    (net (code "56") (name "unconnected-(H2-Pad9)") (class "Default")
      (node (ref "H2") (pin "9") (pinfunction "9_9") (pintype "passive+no_connect"))
    )
    (net (code "57") (name "unconnected-(H2-Pad10)") (class "Default")
      (node (ref "H2") (pin "10") (pinfunction "10_10") (pintype "passive+no_connect"))
    )
    (net (code "58") (name "unconnected-(U1A-AD1{slash}PA18-Pad10)") (class "Default")
      (node (ref "U1") (pin "10") (pinfunction "AD1/PA18_10") (pintype "bidirectional"))
    )
    (net (code "59") (name "unconnected-(U1A-JTAGSEL-Pad50)") (class "Default")
      (node (ref "U1") (pin "50") (pinfunction "JTAGSEL_50") (pintype "input+no_connect"))
    )
    (net (code "60") (name "unconnected-(U1A-PA26-Pad26)") (class "Default")
      (node (ref "U1") (pin "26") (pinfunction "PA26_26") (pintype "bidirectional"))
    )
    (net (code "61") (name "unconnected-(U1A-PA28-Pad38)") (class "Default")
      (node (ref "U1") (pin "38") (pinfunction "PA28_38") (pintype "bidirectional"))
    )
    (net (code "62") (name "unconnected-(U1A-PA29-Pad41)") (class "Default")
      (node (ref "U1") (pin "41") (pinfunction "PA29_41") (pintype "bidirectional"))
    )
    (net (code "63") (name "unconnected-(U1A-PWMH1{slash}PA24-Pad23)") (class "Default")
      (node (ref "U1") (pin "23") (pinfunction "PWMH1/PA24_23") (pintype "bidirectional"))
    )
    (net (code "64") (name "unconnected-(U1A-PWMH2{slash}PA25-Pad25)") (class "Default")
      (node (ref "U1") (pin "25") (pinfunction "PWMH2/PA25_25") (pintype "bidirectional"))
    )
    (net (code "65") (name "unconnected-(U1A-PWML2{slash}PA30-Pad42)") (class "Default")
      (node (ref "U1") (pin "42") (pinfunction "PWML2/PA30_42") (pintype "bidirectional"))
    )
    (net (code "66") (name "unconnected-(U1A-PWML3{slash}PA15-Pad20)") (class "Default")
      (node (ref "U1") (pin "20") (pinfunction "PWML3/PA15_20") (pintype "bidirectional"))
    )
    (net (code "67") (name "unconnected-(U1A-RXD0{slash}PA5-Pad35)") (class "Default")
      (node (ref "U1") (pin "35") (pinfunction "RXD0/PA5_35") (pintype "bidirectional"))
    )
    (net (code "68") (name "unconnected-(U1A-RXD0{slash}PA5-Pad35)_1") (class "Default")
      (node (ref "U1") (pin "35") (pinfunction "RXD0/PA5_35") (pintype "bidirectional"))
    )
    (net (code "69") (name "unconnected-(U1A-TST-Pad40)") (class "Default")
      (node (ref "U1") (pin "40") (pinfunction "TST_40") (pintype "input+no_connect"))
    )
    (net (code "70") (name "unconnected-(U2-BYP-Pad4)") (class "Default")
      (node (ref "U2") (pin "4") (pinfunction "BYP_4") (pintype "passive+no_connect"))
    )
    (net (code "71") (name "unconnected-(U14-NC-Pad6)") (class "Default")
      (node (ref "U14") (pin "6") (pinfunction "NC_6") (pintype "passive+no_connect"))
    )
    (net (code "72") (name "unconnected-(U14-PGOOD-Pad4)") (class "Default")
      (node (ref "U14") (pin "4") (pinfunction "PGOOD_4") (pintype "output+no_connect"))
    )
  )
)
